# rotation_sensor.net
KiCad netlist of a schematic drawn in EAGLE
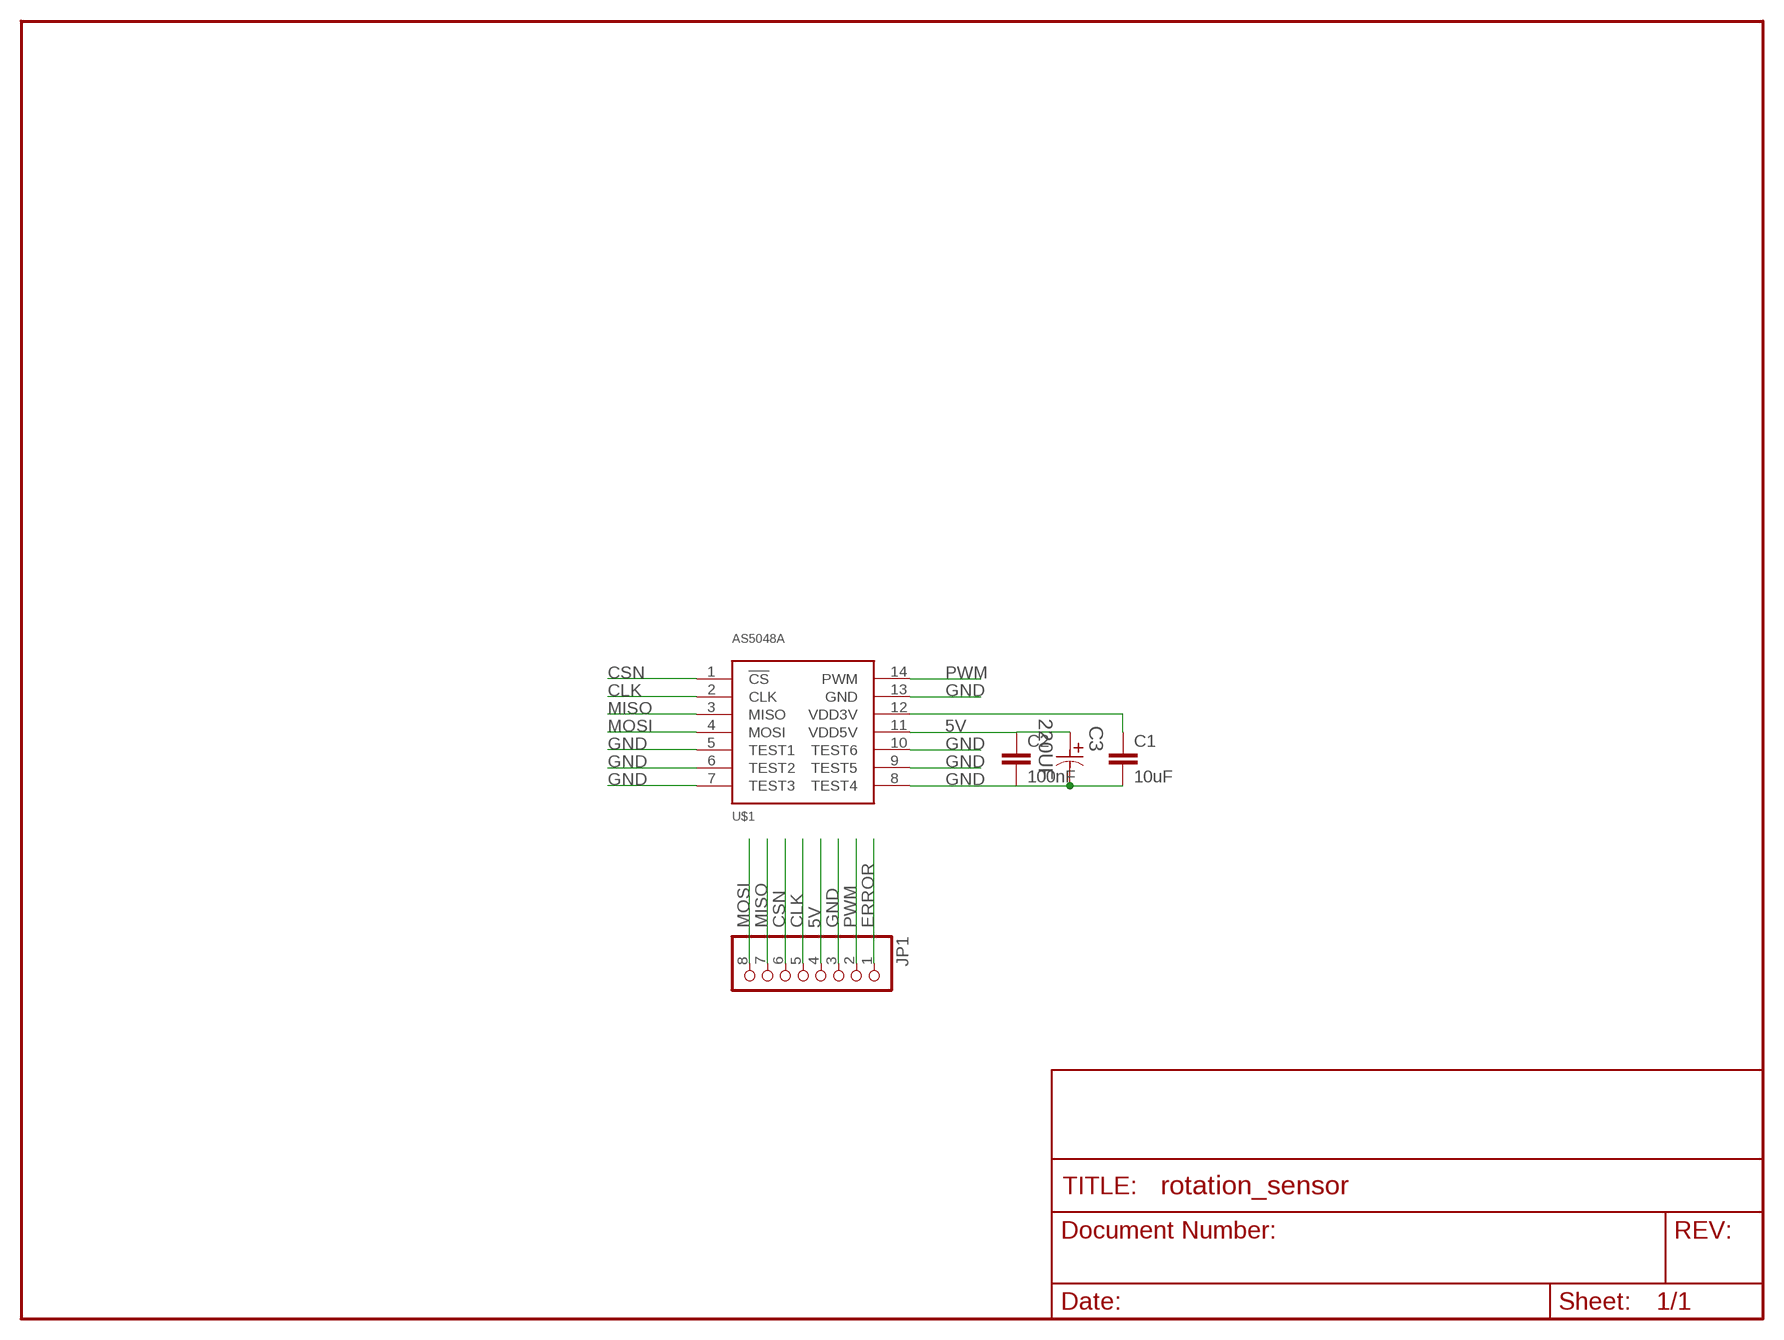
[diagram p0: schematic, sheet 1]

(export (version "E")
  (design (tool "Eeschema 10.0.6"))
  (components
    (comp (ref "C1")
      (value "10uF")
      (footprint "eagle-import:1206")
      (libsource (lib "eagle-import") (part "CAP1206"))
    )
    (comp (ref "C2")
      (value "100nF")
      (footprint "eagle-import:1206")
      (libsource (lib "eagle-import") (part "CAP1206"))
    )
    (comp (ref "C3")
      (value "220UF")
      (footprint "eagle-import:CAPAE830X650N")
      (fields (field (name "MPN") "EEE-FK1C221P") (field (name "TOLERANCE") "±20 %"))
      (libsource (lib "eagle-import") (part "EEE--CASE-EFK1C221P"))
    )
    (comp (ref "JP1")
      (value "PINHD-1X8M")
      (footprint "eagle-import:1X08M")
      (libsource (lib "eagle-import") (part "PINHD-1X8M"))
    )
    (comp (ref "U$1")
      (value "AS5048A")
      (footprint "eagle-import:TSSOP14")
      (libsource (lib "eagle-import") (part "AS5048A"))
    )
  )
  (nets
    (net (code "1") (name "/5V") (class "Default")
      (node (ref "C2") (pin "1") (pinfunction "1_1") (pintype "passive"))
      (node (ref "C3") (pin "1") (pinfunction "1_1") (pintype "passive"))
      (node (ref "JP1") (pin "4") (pinfunction "4_4") (pintype "passive"))
      (node (ref "U$1") (pin "11") (pinfunction "VDD5V_11") (pintype "power_in"))
    )
    (net (code "2") (name "/CLK") (class "Default")
      (node (ref "JP1") (pin "5") (pinfunction "5_5") (pintype "passive"))
      (node (ref "U$1") (pin "2") (pinfunction "CLK_2") (pintype "input"))
    )
    (net (code "3") (name "/CSN") (class "Default")
      (node (ref "JP1") (pin "6") (pinfunction "6_6") (pintype "passive"))
      (node (ref "U$1") (pin "1") (pinfunction "~{CS}_1") (pintype "input"))
    )
    (net (code "4") (name "/ERROR") (class "Default")
      (node (ref "JP1") (pin "1") (pinfunction "1_1") (pintype "passive"))
    )
    (net (code "5") (name "/GND") (class "Default")
      (node (ref "C1") (pin "2") (pinfunction "2_2") (pintype "passive"))
      (node (ref "C2") (pin "2") (pinfunction "2_2") (pintype "passive"))
      (node (ref "C3") (pin "2") (pinfunction "2_2") (pintype "passive"))
      (node (ref "JP1") (pin "3") (pinfunction "3_3") (pintype "passive"))
      (node (ref "U$1") (pin "10") (pinfunction "TEST6_10") (pintype "power_in"))
      (node (ref "U$1") (pin "13") (pinfunction "GND_13") (pintype "power_in"))
      (node (ref "U$1") (pin "5") (pinfunction "TEST1_5") (pintype "power_in"))
      (node (ref "U$1") (pin "6") (pinfunction "TEST2_6") (pintype "power_in"))
      (node (ref "U$1") (pin "7") (pinfunction "TEST3_7") (pintype "power_in"))
      (node (ref "U$1") (pin "8") (pinfunction "TEST4_8") (pintype "power_in"))
      (node (ref "U$1") (pin "9") (pinfunction "TEST5_9") (pintype "power_in"))
    )
    (net (code "6") (name "/MISO") (class "Default")
      (node (ref "JP1") (pin "7") (pinfunction "7_7") (pintype "passive"))
      (node (ref "U$1") (pin "3") (pinfunction "MISO_3") (pintype "output"))
    )
    (net (code "7") (name "/MOSI") (class "Default")
      (node (ref "JP1") (pin "8") (pinfunction "8_8") (pintype "passive"))
      (node (ref "U$1") (pin "4") (pinfunction "MOSI_4") (pintype "input"))
    )
    (net (code "8") (name "/PWM") (class "Default")
      (node (ref "JP1") (pin "2") (pinfunction "2_2") (pintype "passive"))
      (node (ref "U$1") (pin "14") (pinfunction "PWM_14") (pintype "input"))
    )
    (net (code "9") (name "Net-(U$1-VDD3V)") (class "Default")
      (node (ref "C1") (pin "1") (pinfunction "1_1") (pintype "passive"))
      (node (ref "U$1") (pin "12") (pinfunction "VDD3V_12") (pintype "power_in"))
    )
  )
)
